# avr-isp-shield.net
KiCad netlist of a schematic drawn in EAGLE
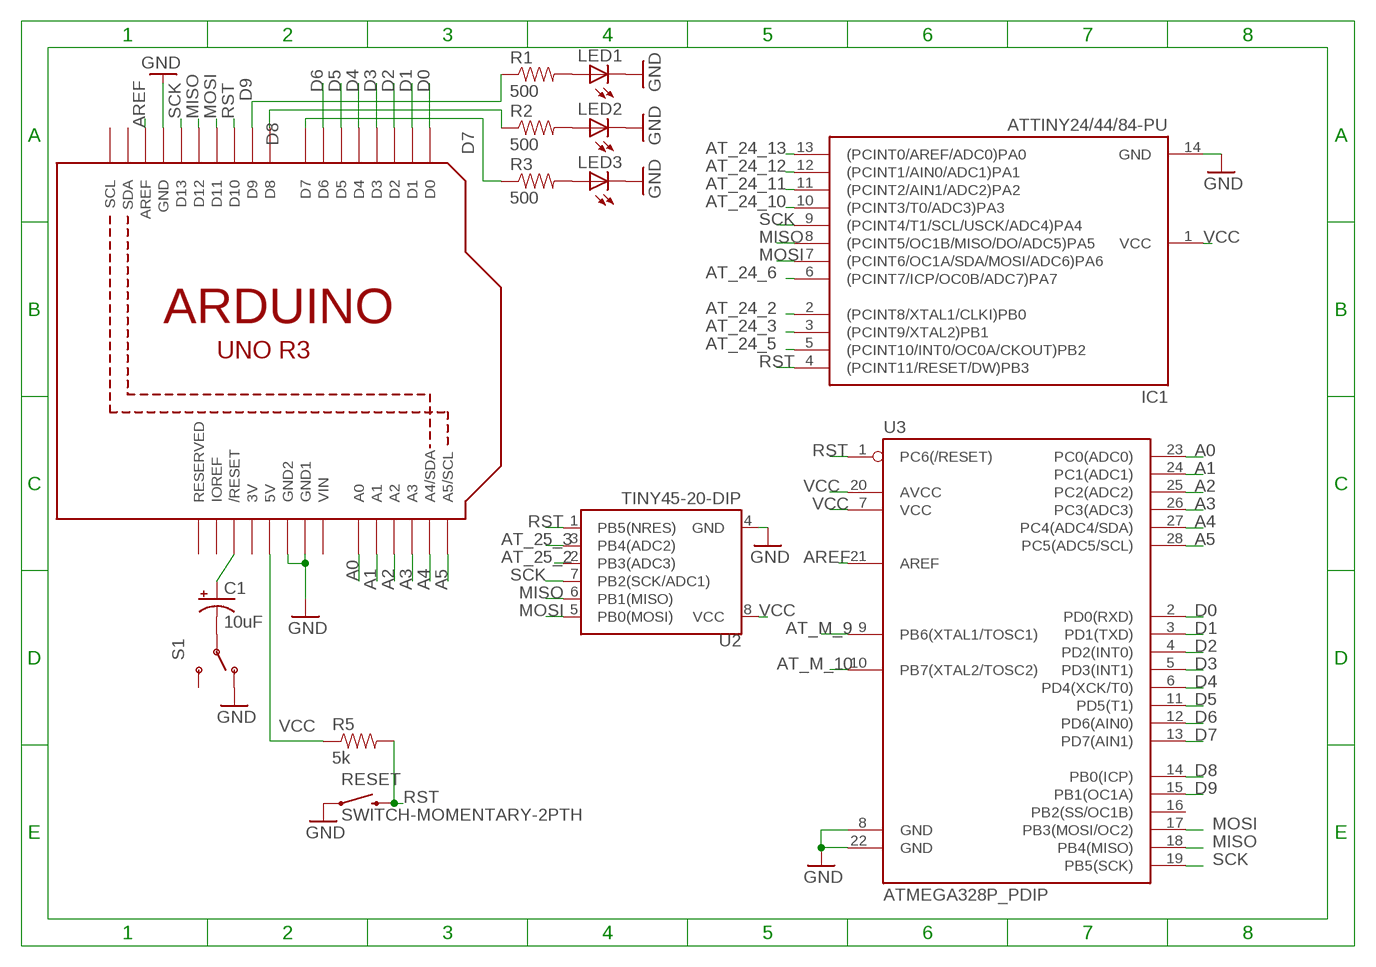
[diagram p0: schematic, sheet 1]

(export (version "E")
  (design (tool "Eeschema 10.0.6"))
  (components
    (comp (ref "C1")
      (value "10uF")
      (footprint "eagle-import:CPOL-RADIAL-10UF-25V")
      (libsource (lib "eagle-import") (part "CAP_POLPTH2"))
    )
    (comp (ref "IC1")
      (value "ATTINY24/44/84-PU")
      (footprint "eagle-import:DIL14")
      (libsource (lib "eagle-import") (part "ATTINY24/44/84-PU"))
    )
    (comp (ref "LED1")
      (value "LED3MM")
      (footprint "eagle-import:LED3MM")
      (libsource (lib "eagle-import") (part "LED3MM"))
    )
    (comp (ref "LED2")
      (value "LED3MM")
      (footprint "eagle-import:LED3MM")
      (libsource (lib "eagle-import") (part "LED3MM"))
    )
    (comp (ref "LED3")
      (value "LED3MM")
      (footprint "eagle-import:LED3MM")
      (libsource (lib "eagle-import") (part "LED3MM"))
    )
    (comp (ref "R1")
      (value "500")
      (footprint "eagle-import:AXIAL-0.3")
      (libsource (lib "eagle-import") (part "RESISTORAXIAL-0.3"))
    )
    (comp (ref "R2")
      (value "500")
      (footprint "eagle-import:AXIAL-0.3")
      (libsource (lib "eagle-import") (part "RESISTORAXIAL-0.3"))
    )
    (comp (ref "R3")
      (value "500")
      (footprint "eagle-import:AXIAL-0.3")
      (libsource (lib "eagle-import") (part "RESISTORAXIAL-0.3"))
    )
    (comp (ref "R5")
      (value "5k")
      (footprint "eagle-import:AXIAL-0.3")
      (libsource (lib "eagle-import") (part "RESISTORAXIAL-0.3"))
    )
    (comp (ref "RESET")
      (value "SWITCH-MOMENTARY-2PTH")
      (footprint "eagle-import:TACTILE-PTH")
      (libsource (lib "eagle-import") (part "SWITCH-MOMENTARY-2PTH"))
    )
    (comp (ref "S1")
      (value "SWITCH-SPDTPTH")
      (footprint "eagle-import:SWITCH-SPDT")
      (libsource (lib "eagle-import") (part "SWITCH-SPDTPTH"))
    )
    (comp (ref "U2")
      (value "TINY45-20-DIP")
      (footprint "eagle-import:DIP08")
      (libsource (lib "eagle-import") (part "ATTINY45TINY45-20-DIP"))
    )
    (comp (ref "U3")
      (value "ATMEGA328P_PDIP")
      (footprint "eagle-import:DIL28-3")
      (libsource (lib "eagle-import") (part "ATMEGA328P_PDIP"))
    )
    (comp (ref "U4")
      (value "ARDUINOR3-DIMENSION")
      (footprint "eagle-import:ARDUINOR3")
      (libsource (lib "eagle-import") (part "ARDUINOR3-DIMENSION"))
    )
  )
  (nets
    (net (code "1") (name "/3V") (class "Default")
      (node (ref "U4") (pin "3V") (pinfunction "3V_3V") (pintype "power_in"))
    )
    (net (code "2") (name "/A0") (class "Default")
      (node (ref "U3") (pin "23") (pinfunction "PC0(ADC0)_23") (pintype "bidirectional"))
      (node (ref "U4") (pin "A0") (pinfunction "A0_A0") (pintype "bidirectional"))
    )
    (net (code "3") (name "/A1") (class "Default")
      (node (ref "U3") (pin "24") (pinfunction "PC1(ADC1)_24") (pintype "bidirectional"))
      (node (ref "U4") (pin "A1") (pinfunction "A1_A1") (pintype "bidirectional"))
    )
    (net (code "4") (name "/A2") (class "Default")
      (node (ref "U3") (pin "25") (pinfunction "PC2(ADC2)_25") (pintype "bidirectional"))
      (node (ref "U4") (pin "A2") (pinfunction "A2_A2") (pintype "bidirectional"))
    )
    (net (code "5") (name "/A3") (class "Default")
      (node (ref "U3") (pin "26") (pinfunction "PC3(ADC3)_26") (pintype "bidirectional"))
      (node (ref "U4") (pin "A3") (pinfunction "A3_A3") (pintype "bidirectional"))
    )
    (net (code "6") (name "/A4") (class "Default")
      (node (ref "U3") (pin "27") (pinfunction "PC4(ADC4/SDA)_27") (pintype "bidirectional"))
      (node (ref "U4") (pin "A4") (pinfunction "A4/SDA_A4") (pintype "bidirectional"))
    )
    (net (code "7") (name "/A5") (class "Default")
      (node (ref "U3") (pin "28") (pinfunction "PC5(ADC5/SCL)_28") (pintype "bidirectional"))
      (node (ref "U4") (pin "A5") (pinfunction "A5/SCL_A5") (pintype "bidirectional"))
    )
    (net (code "8") (name "/AREF") (class "Default")
      (node (ref "U3") (pin "21") (pinfunction "AREF_21") (pintype "bidirectional"))
      (node (ref "U4") (pin "AREF") (pinfunction "AREF_AREF") (pintype "bidirectional"))
    )
    (net (code "9") (name "/AT_24_2") (class "Default")
      (node (ref "IC1") (pin "2") (pinfunction "(PCINT8/XTAL1/CLKI)PB0_2") (pintype "bidirectional"))
    )
    (net (code "10") (name "/AT_24_3") (class "Default")
      (node (ref "IC1") (pin "3") (pinfunction "(PCINT9/XTAL2)PB1_3") (pintype "bidirectional"))
    )
    (net (code "11") (name "/AT_24_5") (class "Default")
      (node (ref "IC1") (pin "5") (pinfunction "(PCINT10/INT0/OC0A/CKOUT)PB2_5") (pintype "bidirectional"))
    )
    (net (code "12") (name "/AT_24_6") (class "Default")
      (node (ref "IC1") (pin "6") (pinfunction "(PCINT7/ICP/OC0B/ADC7)PA7_6") (pintype "bidirectional"))
    )
    (net (code "13") (name "/AT_24_10") (class "Default")
      (node (ref "IC1") (pin "10") (pinfunction "(PCINT3/T0/ADC3)PA3_10") (pintype "bidirectional"))
    )
    (net (code "14") (name "/AT_24_11") (class "Default")
      (node (ref "IC1") (pin "11") (pinfunction "(PCINT2/AIN1/ADC2)PA2_11") (pintype "bidirectional"))
    )
    (net (code "15") (name "/AT_24_12") (class "Default")
      (node (ref "IC1") (pin "12") (pinfunction "(PCINT1/AIN0/ADC1)PA1_12") (pintype "bidirectional"))
    )
    (net (code "16") (name "/AT_24_13") (class "Default")
      (node (ref "IC1") (pin "13") (pinfunction "(PCINT0/AREF/ADC0)PA0_13") (pintype "bidirectional"))
    )
    (net (code "17") (name "/AT_25_2") (class "Default")
      (node (ref "U2") (pin "2") (pinfunction "PB3(ADC3)_2") (pintype "bidirectional"))
    )
    (net (code "18") (name "/AT_25_3") (class "Default")
      (node (ref "U2") (pin "3") (pinfunction "PB4(ADC2)_3") (pintype "bidirectional"))
    )
    (net (code "19") (name "/AT_M_9") (class "Default")
      (node (ref "U3") (pin "9") (pinfunction "PB6(XTAL1/TOSC1)_9") (pintype "bidirectional"))
    )
    (net (code "20") (name "/AT_M_10") (class "Default")
      (node (ref "U3") (pin "10") (pinfunction "PB7(XTAL2/TOSC2)_10") (pintype "bidirectional"))
    )
    (net (code "21") (name "/D0") (class "Default")
      (node (ref "U3") (pin "2") (pinfunction "PD0(RXD)_2") (pintype "bidirectional"))
      (node (ref "U4") (pin "D0") (pinfunction "D0_D0") (pintype "bidirectional"))
    )
    (net (code "22") (name "/D1") (class "Default")
      (node (ref "U3") (pin "3") (pinfunction "PD1(TXD)_3") (pintype "bidirectional"))
      (node (ref "U4") (pin "D1") (pinfunction "D1_D1") (pintype "bidirectional"))
    )
    (net (code "23") (name "/D2") (class "Default")
      (node (ref "U3") (pin "4") (pinfunction "PD2(INT0)_4") (pintype "bidirectional"))
      (node (ref "U4") (pin "D2") (pinfunction "D2_D2") (pintype "bidirectional"))
    )
    (net (code "24") (name "/D3") (class "Default")
      (node (ref "U3") (pin "5") (pinfunction "PD3(INT1)_5") (pintype "bidirectional"))
      (node (ref "U4") (pin "D3") (pinfunction "D3_D3") (pintype "bidirectional"))
    )
    (net (code "25") (name "/D4") (class "Default")
      (node (ref "U3") (pin "6") (pinfunction "PD4(XCK/T0)_6") (pintype "bidirectional"))
      (node (ref "U4") (pin "D4") (pinfunction "D4_D4") (pintype "bidirectional"))
    )
    (net (code "26") (name "/D5") (class "Default")
      (node (ref "U3") (pin "11") (pinfunction "PD5(T1)_11") (pintype "bidirectional"))
      (node (ref "U4") (pin "D5") (pinfunction "D5_D5") (pintype "bidirectional"))
    )
    (net (code "27") (name "/D6") (class "Default")
      (node (ref "U3") (pin "12") (pinfunction "PD6(AIN0)_12") (pintype "bidirectional"))
      (node (ref "U4") (pin "D6") (pinfunction "D6_D6") (pintype "bidirectional"))
    )
    (net (code "28") (name "/D7") (class "Default")
      (node (ref "R3") (pin "P$1") (pinfunction "1_P$1") (pintype "passive"))
      (node (ref "U3") (pin "13") (pinfunction "PD7(AIN1)_13") (pintype "bidirectional"))
      (node (ref "U4") (pin "D7") (pinfunction "D7_D7") (pintype "bidirectional"))
    )
    (net (code "29") (name "/D8") (class "Default")
      (node (ref "R2") (pin "P$1") (pinfunction "1_P$1") (pintype "passive"))
      (node (ref "U3") (pin "14") (pinfunction "PB0(ICP)_14") (pintype "bidirectional"))
      (node (ref "U4") (pin "D8") (pinfunction "D8_D8") (pintype "bidirectional"))
    )
    (net (code "30") (name "/D9") (class "Default")
      (node (ref "R1") (pin "P$1") (pinfunction "1_P$1") (pintype "passive"))
      (node (ref "U3") (pin "15") (pinfunction "PB1(OC1A)_15") (pintype "bidirectional"))
      (node (ref "U4") (pin "D9") (pinfunction "D9_D9") (pintype "bidirectional"))
    )
    (net (code "31") (name "/MISO") (class "Default")
      (node (ref "IC1") (pin "8") (pinfunction "(PCINT5/OC1B/MISO/DO/ADC5)PA5_8") (pintype "bidirectional"))
      (node (ref "U2") (pin "6") (pinfunction "PB1(MISO)_6") (pintype "bidirectional"))
      (node (ref "U3") (pin "18") (pinfunction "PB4(MISO)_18") (pintype "bidirectional"))
      (node (ref "U4") (pin "D12") (pinfunction "D12_D12") (pintype "bidirectional"))
    )
    (net (code "32") (name "/MOSI") (class "Default")
      (node (ref "IC1") (pin "7") (pinfunction "(PCINT6/OC1A/SDA/MOSI/ADC6)PA6_7") (pintype "bidirectional"))
      (node (ref "U2") (pin "5") (pinfunction "PB0(MOSI)_5") (pintype "bidirectional"))
      (node (ref "U3") (pin "17") (pinfunction "PB3(MOSI/OC2)_17") (pintype "bidirectional"))
      (node (ref "U4") (pin "D11") (pinfunction "D11_D11") (pintype "bidirectional"))
    )
    (net (code "33") (name "/RST") (class "Default")
      (node (ref "IC1") (pin "4") (pinfunction "(PCINT11/RESET/DW)PB3_4") (pintype "bidirectional"))
      (node (ref "R5") (pin "P$2") (pinfunction "2_P$2") (pintype "passive"))
      (node (ref "RESET") (pin "3") (pinfunction "2_3") (pintype "passive"))
      (node (ref "U2") (pin "1") (pinfunction "PB5(NRES)_1") (pintype "bidirectional"))
      (node (ref "U3") (pin "1") (pinfunction "PC6(/RESET)_1") (pintype "bidirectional"))
      (node (ref "U4") (pin "D10") (pinfunction "D10_D10") (pintype "bidirectional"))
    )
    (net (code "34") (name "/SCK") (class "Default")
      (node (ref "IC1") (pin "9") (pinfunction "(PCINT4/T1/SCL/USCK/ADC4)PA4_9") (pintype "bidirectional"))
      (node (ref "U2") (pin "7") (pinfunction "PB2(SCK/ADC1)_7") (pintype "bidirectional"))
      (node (ref "U3") (pin "19") (pinfunction "PB5(SCK)_19") (pintype "bidirectional"))
      (node (ref "U4") (pin "D13") (pinfunction "D13_D13") (pintype "bidirectional"))
    )
    (net (code "35") (name "/VCC") (class "Default")
      (node (ref "IC1") (pin "1") (pinfunction "VCC_1") (pintype "power_in"))
      (node (ref "R5") (pin "P$1") (pinfunction "1_P$1") (pintype "passive"))
      (node (ref "U2") (pin "8") (pinfunction "VCC_8") (pintype "bidirectional"))
      (node (ref "U3") (pin "20") (pinfunction "AVCC_20") (pintype "bidirectional"))
      (node (ref "U3") (pin "7") (pinfunction "VCC_7") (pintype "bidirectional"))
      (node (ref "U4") (pin "5V") (pinfunction "5V_5V") (pintype "power_in"))
    )
    (net (code "36") (name "/VIN") (class "Default")
      (node (ref "U4") (pin "VIN") (pinfunction "VIN_VIN") (pintype "power_in"))
    )
    (net (code "37") (name "GND") (class "Default")
      (node (ref "IC1") (pin "14") (pinfunction "GND_14") (pintype "power_in"))
      (node (ref "LED1") (pin "K") (pinfunction "C_K") (pintype "passive"))
      (node (ref "LED2") (pin "K") (pinfunction "C_K") (pintype "passive"))
      (node (ref "LED3") (pin "K") (pinfunction "C_K") (pintype "passive"))
      (node (ref "RESET") (pin "1") (pinfunction "1_1") (pintype "passive"))
      (node (ref "S1") (pin "1") (pinfunction "O_1") (pintype "passive"))
      (node (ref "U2") (pin "4") (pinfunction "GND_4") (pintype "bidirectional"))
      (node (ref "U3") (pin "22") (pinfunction "GND_22") (pintype "bidirectional"))
      (node (ref "U3") (pin "8") (pinfunction "GND_8") (pintype "bidirectional"))
      (node (ref "U4") (pin "GND1") (pinfunction "GND1_GND1") (pintype "power_in"))
      (node (ref "U4") (pin "GND2") (pinfunction "GND2_GND2") (pintype "power_in"))
    )
    (net (code "38") (name "Net-(C1-+)") (class "Default")
      (node (ref "C1") (pin "1") (pinfunction "+_1") (pintype "passive"))
      (node (ref "U4") (pin "RESET") (pinfunction "/RESET_RESET") (pintype "bidirectional"))
    )
    (net (code "39") (name "Net-(C1--)") (class "Default")
      (node (ref "C1") (pin "2") (pinfunction "-_2") (pintype "passive"))
      (node (ref "S1") (pin "2") (pinfunction "P_2") (pintype "passive"))
    )
    (net (code "40") (name "Net-(R1-2)") (class "Default")
      (node (ref "LED1") (pin "A") (pinfunction "A_A") (pintype "passive"))
      (node (ref "R1") (pin "P$2") (pinfunction "2_P$2") (pintype "passive"))
    )
    (net (code "41") (name "Net-(R2-2)") (class "Default")
      (node (ref "LED2") (pin "A") (pinfunction "A_A") (pintype "passive"))
      (node (ref "R2") (pin "P$2") (pinfunction "2_P$2") (pintype "passive"))
    )
    (net (code "42") (name "Net-(R3-2)") (class "Default")
      (node (ref "LED3") (pin "A") (pinfunction "A_A") (pintype "passive"))
      (node (ref "R3") (pin "P$2") (pinfunction "2_P$2") (pintype "passive"))
    )
    (net (code "43") (name "unconnected-(S1-S-Pad3)") (class "Default")
      (node (ref "S1") (pin "3") (pinfunction "S_3") (pintype "passive"))
    )
    (net (code "44") (name "unconnected-(U3-PB2(SS{slash}OC1B)-Pad16)") (class "Default")
      (node (ref "U3") (pin "16") (pinfunction "PB2(SS/OC1B)_16") (pintype "bidirectional"))
    )
    (net (code "45") (name "unconnected-(U4-PadGND)") (class "Default")
      (node (ref "U4") (pin "GND") (pinfunction "GND_GND") (pintype "power_in"))
    )
    (net (code "46") (name "unconnected-(U4-PadIOREF)") (class "Default")
      (node (ref "U4") (pin "IOREF") (pinfunction "IOREF_IOREF") (pintype "output"))
    )
    (net (code "47") (name "unconnected-(U4-PadRESERVED)") (class "Default")
      (node (ref "U4") (pin "RESERVED") (pinfunction "RESERVED_RESERVED") (pintype "no_connect"))
    )
    (net (code "48") (name "unconnected-(U4-PadSCL)") (class "Default")
      (node (ref "U4") (pin "SCL") (pinfunction "SCL_SCL") (pintype "bidirectional"))
    )
    (net (code "49") (name "unconnected-(U4-PadSDA)") (class "Default")
      (node (ref "U4") (pin "SDA") (pinfunction "SDA_SDA") (pintype "bidirectional"))
    )
  )
)
